# Main.net
KiCad netlist of a schematic drawn in Altium Designer
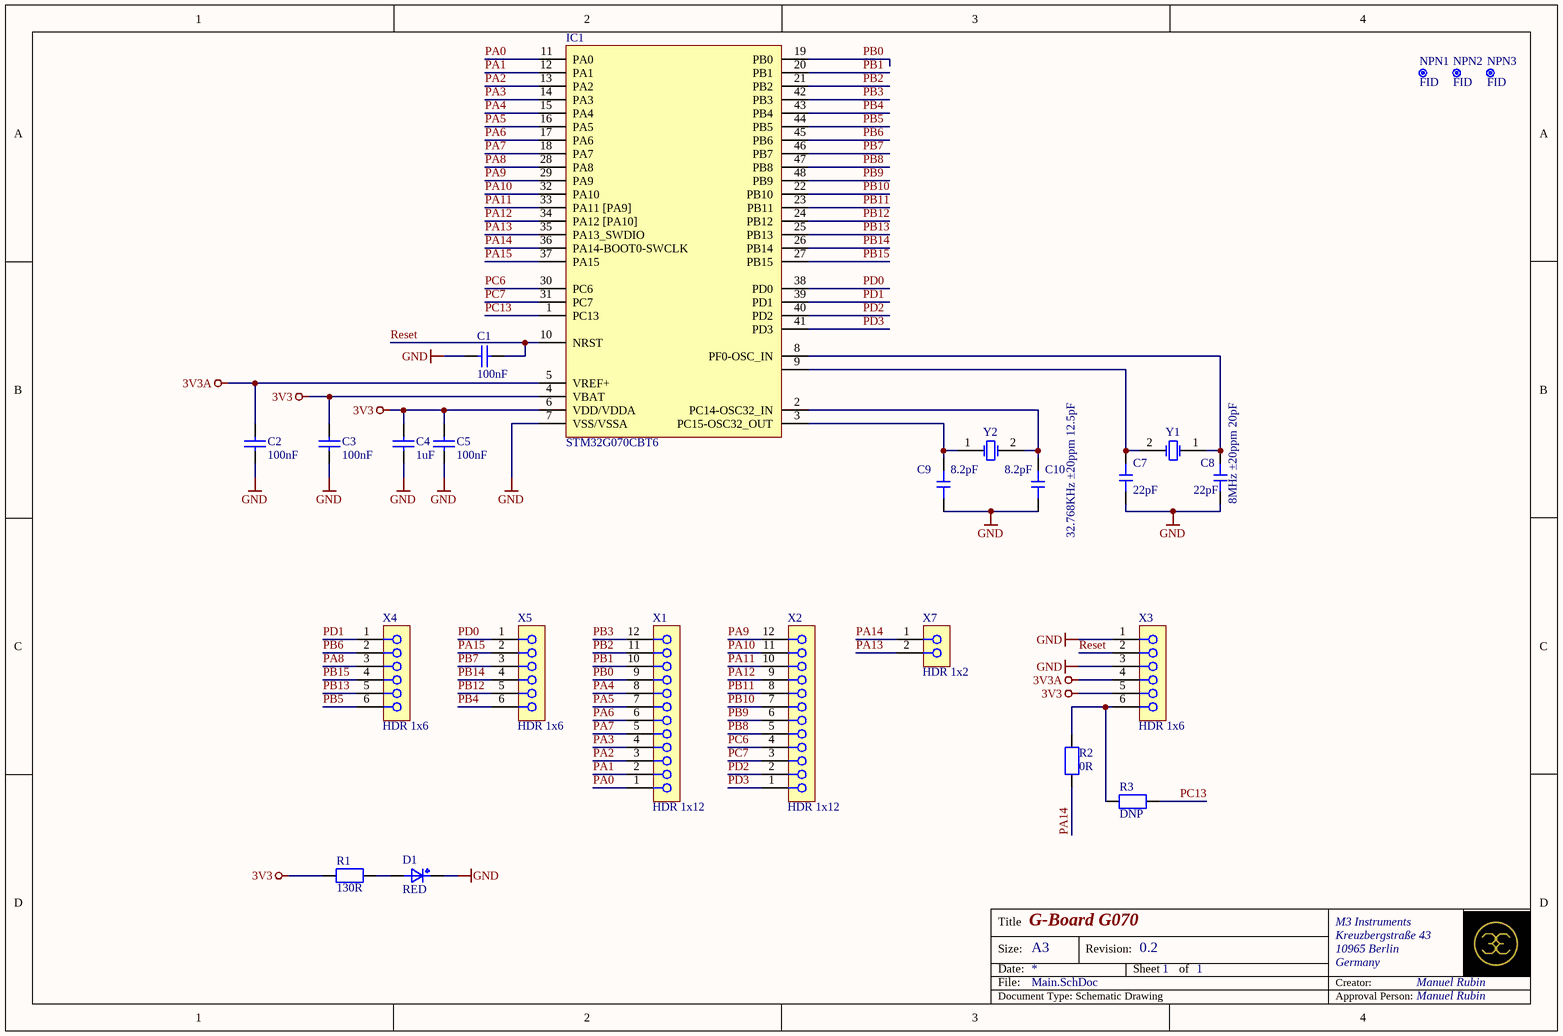
[diagram p0: Main.SchDoc]

(export (version "E")
  (design (tool "Eeschema 10.0.6"))
  (components
    (comp (ref "C1")
      (value "100nF")
      (footprint "CAPC1005X55")
      (description "X7R 100nF ±10% 16V 0402 Multilayer Ceramic Capacitors MLCC - SMD/SMT ROHS")
      (fields
        (field (name "MANUFACTURER") "Samsung Electro-Mechanics")
        (field (name "MANUFACTURER PART NUMBER") "CL05B104KO5NNNC")
      )
      (libsource (lib "Caps") (part "CAP_100nF_0402"))
    )
    (comp (ref "C2")
      (value "100nF")
      (footprint "CAPC1005X55")
      (description "X7R 100nF ±10% 16V 0402 Multilayer Ceramic Capacitors MLCC - SMD/SMT ROHS")
      (fields
        (field (name "MANUFACTURER") "Samsung Electro-Mechanics")
        (field (name "MANUFACTURER PART NUMBER") "CL05B104KO5NNNC")
      )
      (libsource (lib "Caps") (part "CAP_100nF_0402"))
    )
    (comp (ref "C3")
      (value "100nF")
      (footprint "CAPC1005X55")
      (description "X7R 100nF ±10% 16V 0402 Multilayer Ceramic Capacitors MLCC - SMD/SMT ROHS")
      (fields
        (field (name "MANUFACTURER") "Samsung Electro-Mechanics")
        (field (name "MANUFACTURER PART NUMBER") "CL05B104KO5NNNC")
      )
      (libsource (lib "Caps") (part "CAP_100nF_0402"))
    )
    (comp (ref "C4")
      (value "1uF")
      (footprint "CAPC1005X55")
      (description "X5R 25V ±10% 1uF 0402 Multilayer Ceramic Capacitors MLCC - SMD/SMT ROHS")
      (fields
        (field (name "MANUFACTURER") "Samsung Electro-Mechanics")
        (field (name "MANUFACTURER PART NUMBER") "CL05A105KA5NQNC")
      )
      (libsource (lib "Caps") (part "CAP_1uF_0402"))
    )
    (comp (ref "C5")
      (value "100nF")
      (footprint "CAPC1005X55")
      (description "X7R 100nF ±10% 16V 0402 Multilayer Ceramic Capacitors MLCC - SMD/SMT ROHS")
      (fields
        (field (name "MANUFACTURER") "Samsung Electro-Mechanics")
        (field (name "MANUFACTURER PART NUMBER") "CL05B104KO5NNNC")
      )
      (libsource (lib "Caps") (part "CAP_100nF_0402"))
    )
    (comp (ref "C7")
      (value "22pF")
      (footprint "CAPC1608X95N")
      (description "Chip capacitors")
      (fields
        (field (name "MANUFACTURER") "Samsung Electro-Mechanics")
        (field (name "MANUFACTURER PART NUMBER") "CL10C220JB8NNNC")
      )
      (libsource (lib "Caps") (part "CAP_22pF_50V_0603"))
    )
    (comp (ref "C8")
      (value "22pF")
      (footprint "CAPC1608X95N")
      (description "Chip capacitors")
      (fields
        (field (name "MANUFACTURER") "Samsung Electro-Mechanics")
        (field (name "MANUFACTURER PART NUMBER") "CL10C220JB8NNNC")
      )
      (libsource (lib "Caps") (part "CAP_22pF_50V_0603"))
    )
    (comp (ref "C9")
      (value "8.2pF")
      (footprint "CAPC1608X95N")
      (description "Multilayer Ceramic Capacitors MLCC - SMD/SMT 0402 8.0pF 50volts C0G +/-0.5pF")
      (fields
        (field (name "MANUFACTURER") "Guangdong Fenghua Advanced Tech")
        (field (name "MANUFACTURER PART NUMBER") "0603CG8R2C500NT")
      )
      (libsource (lib "Caps") (part "CAP_8p2_50V_0603"))
    )
    (comp (ref "C10")
      (value "8.2pF")
      (footprint "CAPC1608X95N")
      (description "Multilayer Ceramic Capacitors MLCC - SMD/SMT 0402 8.0pF 50volts C0G +/-0.5pF")
      (fields
        (field (name "MANUFACTURER") "Guangdong Fenghua Advanced Tech")
        (field (name "MANUFACTURER PART NUMBER") "0603CG8R2C500NT")
      )
      (libsource (lib "Caps") (part "CAP_8p2_50V_0603"))
    )
    (comp (ref "D1")
      (value "RED")
      (footprint "WL-SMCW_0805")
      (description "Standard LEDs - SMD WL-SMCW SMDMono TpVw Waterclr 0805 Red")
      (fields
        (field (name "MANUFACTURER") "Wurth Elektronik")
        (field (name "MANUFACTURER PART NUMBER") "150080RS75000")
      )
      (libsource (lib "Diodes") (part "LED_0805_RED_AK"))
    )
    (comp (ref "IC1")
      (value "STM32G070CBT6")
      (footprint "LQFP-48_7x7x05P")
      (fields (field (name "MANUFACTURER") "STMicroelectronics"))
      (libsource (lib "ICs") (part "STM32G070CBT6"))
    )
    (comp (ref "NPN1")
      (value "FID")
      (footprint "Fiducial_1mm")
      (libsource (lib "MISC") (part "Fiducial_1mm"))
    )
    (comp (ref "NPN2")
      (value "FID")
      (footprint "Fiducial_1mm")
      (libsource (lib "MISC") (part "Fiducial_1mm"))
    )
    (comp (ref "NPN3")
      (value "FID")
      (footprint "Fiducial_1mm")
      (libsource (lib "MISC") (part "Fiducial_1mm"))
    )
    (comp (ref "R1")
      (value "130R")
      (footprint "RESC2012X70N")
      (description "Dickfilmwiderstände - SMD 1/8watt 130ohms 1% 100ppm")
      (fields
        (field (name "MANUFACTURER") "Vishay / Dale")
        (field (name "MANUFACTURER PART NUMBER") "CRCW0805130RFKEA")
      )
      (libsource (lib "Resistors") (part "RES_130R_0805"))
    )
    (comp (ref "R2")
      (value "0R")
      (footprint "RESC1608X55N")
      (description "Thick Film Resistors - SMD 1/10watt ZEROohm Jumper")
      (fields
        (field (name "MANUFACTURER") "Vishay")
        (field (name "MANUFACTURER PART NUMBER") "CRCW06030000Z0EA")
      )
      (libsource (lib "Resistors") (part "RES_0R_0603"))
    )
    (comp (ref "R3")
      (value "DNP")
      (footprint "RESC1608X55N")
      (description "Resistor SMD 0603 - not populated")
      (libsource (lib "Resistors") (part "RES_DNF_0603"))
    )
    (comp (ref "X1")
      (value "HDR 1x12")
      (footprint "61301211121_no")
      (description "Board-to-Board-Steckverbinder, 2.54 mm, 12 Kontakt(e), Stiftleiste 1-Reihig")
      (fields (field (name "MANUFACTURER") "WE") (field (name "MANUFACTURER PART NUMBER") "61301211121"))
      (libsource (lib "Connectors") (part "CON_HEADER_1X12_no_overlay"))
    )
    (comp (ref "X2")
      (value "HDR 1x12")
      (footprint "61301211121_no")
      (description "Board-to-Board-Steckverbinder, 2.54 mm, 12 Kontakt(e), Stiftleiste 1-Reihig")
      (fields (field (name "MANUFACTURER") "WE") (field (name "MANUFACTURER PART NUMBER") "61301211121"))
      (libsource (lib "Connectors") (part "CON_HEADER_1X12_no_overlay"))
    )
    (comp (ref "X3")
      (value "HDR 1x6")
      (footprint "61300611121_no")
      (description "Board-to-Board-Steckverbinder, 2.54 mm, 6 Kontakt(e), Stiftleiste 1-Reihig")
      (fields (field (name "MANUFACTURER") "WE") (field (name "MANUFACTURER PART NUMBER") "61300611121"))
      (libsource (lib "Connectors") (part "CON_HEADER_1X6_no_overlay"))
    )
    (comp (ref "X4")
      (value "HDR 1x6")
      (footprint "61300611121_no")
      (description "Board-to-Board-Steckverbinder, 2.54 mm, 6 Kontakt(e), Stiftleiste 1-Reihig")
      (fields (field (name "MANUFACTURER") "WE") (field (name "MANUFACTURER PART NUMBER") "61300611121"))
      (libsource (lib "Connectors") (part "CON_HEADER_1X6_no_overlay"))
    )
    (comp (ref "X5")
      (value "HDR 1x6")
      (footprint "61300611121_no")
      (description "Board-to-Board-Steckverbinder, 2.54 mm, 6 Kontakt(e), Stiftleiste 1-Reihig")
      (fields (field (name "MANUFACTURER") "WE") (field (name "MANUFACTURER PART NUMBER") "61300611121"))
      (libsource (lib "Connectors") (part "CON_HEADER_1X6_no_overlay"))
    )
    (comp (ref "X7")
      (value "HDR 1x2")
      (footprint "CON_HEADER2.54_1x2W_no")
      (description "Board-to-Board-Steckverbinder, 2.54 mm, 2 Kontakt(e), Stiftleiste 1-Reihig")
      (fields
        (field (name "MANUFACTURER") "Samtec")
        (field (name "MANUFACTURER PART NUMBER") "TSW-102-07-T-S")
      )
      (libsource (lib "Connectors") (part "CON_HEADER_1X2_no_overlay"))
    )
    (comp (ref "Y1")
      (value "8MHz ±20ppm 20pF")
      (footprint "SMD-5032_2P")
      (description "8MHz SMD Crystal Resonator 20pF ±10ppm ±50ppm -40℃~+85℃ SMD5032-2P Crystals ROHS")
      (fields
        (field (name "MANUFACTURER") "Yangxing Tech")
        (field (name "MANUFACTURER PART NUMBER") "X50328MSB2GI")
      )
      (libsource (lib "MISC") (part "SMD-5032_2P 8MHz 20ppm 20pF"))
    )
    (comp (ref "Y2")
      (value "32.768KHz ±20ppm 12.5pF")
      (footprint "SMD-3215_2P FC - 135")
      (description "32.768kHz SMD Crystal Resonator 12.5pF 70kΩ ±20ppm -40℃~+85℃ SMD3215-2P Crystals ROHS")
      (fields
        (field (name "MANUFACTURER") "Seiko Epson")
        (field (name "MANUFACTURER PART NUMBER") "Q13FC1350000400")
      )
      (libsource (lib "MISC") (part "SMD-3215_2P 32.768KHz 20ppm 12.5pF"))
    )
  )
  (nets
    (net (code "1") (name "/PA0") (class "Default")
      (node (ref "IC1") (pin "11") (pinfunction "PA0_11") (pintype "passive"))
      (node (ref "X1") (pin "1") (pinfunction "1_1") (pintype "passive"))
    )
    (net (code "2") (name "/PA1") (class "Default")
      (node (ref "IC1") (pin "12") (pinfunction "PA1_12") (pintype "passive"))
      (node (ref "X1") (pin "2") (pinfunction "2_2") (pintype "passive"))
    )
    (net (code "3") (name "/PA2") (class "Default")
      (node (ref "IC1") (pin "13") (pinfunction "PA2_13") (pintype "passive"))
      (node (ref "X1") (pin "3") (pinfunction "3_3") (pintype "passive"))
    )
    (net (code "4") (name "/PA3") (class "Default")
      (node (ref "IC1") (pin "14") (pinfunction "PA3_14") (pintype "passive"))
      (node (ref "X1") (pin "4") (pinfunction "4_4") (pintype "passive"))
    )
    (net (code "5") (name "/PA4") (class "Default")
      (node (ref "IC1") (pin "15") (pinfunction "PA4_15") (pintype "passive"))
      (node (ref "X1") (pin "8") (pinfunction "8_8") (pintype "passive"))
    )
    (net (code "6") (name "/PA5") (class "Default")
      (node (ref "IC1") (pin "16") (pinfunction "PA5_16") (pintype "passive"))
      (node (ref "X1") (pin "7") (pinfunction "7_7") (pintype "passive"))
    )
    (net (code "7") (name "/PA6") (class "Default")
      (node (ref "IC1") (pin "17") (pinfunction "PA6_17") (pintype "passive"))
      (node (ref "X1") (pin "6") (pinfunction "6_6") (pintype "passive"))
    )
    (net (code "8") (name "/PA7") (class "Default")
      (node (ref "IC1") (pin "18") (pinfunction "PA7_18") (pintype "passive"))
      (node (ref "X1") (pin "5") (pinfunction "5_5") (pintype "passive"))
    )
    (net (code "9") (name "/PA8") (class "Default")
      (node (ref "IC1") (pin "28") (pinfunction "PA8_28") (pintype "passive"))
      (node (ref "X4") (pin "3") (pinfunction "3_3") (pintype "passive"))
    )
    (net (code "10") (name "/PA9") (class "Default")
      (node (ref "IC1") (pin "29") (pinfunction "PA9_29") (pintype "passive"))
      (node (ref "X2") (pin "12") (pinfunction "12_12") (pintype "passive"))
    )
    (net (code "11") (name "/PA10") (class "Default")
      (node (ref "IC1") (pin "32") (pinfunction "PA10_32") (pintype "passive"))
      (node (ref "X2") (pin "11") (pinfunction "11_11") (pintype "passive"))
    )
    (net (code "12") (name "/PA11") (class "Default")
      (node (ref "IC1") (pin "33") (pinfunction "PA11_[PA9]_33") (pintype "passive"))
      (node (ref "X2") (pin "10") (pinfunction "10_10") (pintype "passive"))
    )
    (net (code "13") (name "/PA12") (class "Default")
      (node (ref "IC1") (pin "34") (pinfunction "PA12_[PA10]_34") (pintype "passive"))
      (node (ref "X2") (pin "9") (pinfunction "9_9") (pintype "passive"))
    )
    (net (code "14") (name "/PA13") (class "Default")
      (node (ref "IC1") (pin "35") (pinfunction "PA13_SWDIO_35") (pintype "power_in"))
      (node (ref "X7") (pin "2") (pinfunction "2_2") (pintype "passive"))
    )
    (net (code "15") (name "/PA14") (class "Default")
      (node (ref "IC1") (pin "36") (pinfunction "PA14-BOOT0-SWCLK_36") (pintype "power_in"))
      (node (ref "R2") (pin "1") (pinfunction "1_1") (pintype "passive"))
      (node (ref "X7") (pin "1") (pinfunction "1_1") (pintype "passive"))
    )
    (net (code "16") (name "/PA15") (class "Default")
      (node (ref "IC1") (pin "37") (pinfunction "PA15_37") (pintype "passive"))
      (node (ref "X5") (pin "2") (pinfunction "2_2") (pintype "passive"))
    )
    (net (code "17") (name "/PB0") (class "Default")
      (node (ref "IC1") (pin "19") (pinfunction "PB0_19") (pintype "passive"))
      (node (ref "X1") (pin "9") (pinfunction "9_9") (pintype "passive"))
    )
    (net (code "18") (name "/PB1") (class "Default")
      (node (ref "IC1") (pin "20") (pinfunction "PB1_20") (pintype "passive"))
      (node (ref "X1") (pin "10") (pinfunction "10_10") (pintype "passive"))
    )
    (net (code "19") (name "/PB2") (class "Default")
      (node (ref "IC1") (pin "21") (pinfunction "PB2_21") (pintype "passive"))
      (node (ref "X1") (pin "11") (pinfunction "11_11") (pintype "passive"))
    )
    (net (code "20") (name "/PB3") (class "Default")
      (node (ref "IC1") (pin "42") (pinfunction "PB3_42") (pintype "passive"))
      (node (ref "X1") (pin "12") (pinfunction "12_12") (pintype "passive"))
    )
    (net (code "21") (name "/PB4") (class "Default")
      (node (ref "IC1") (pin "43") (pinfunction "PB4_43") (pintype "passive"))
      (node (ref "X5") (pin "6") (pinfunction "6_6") (pintype "passive"))
    )
    (net (code "22") (name "/PB5") (class "Default")
      (node (ref "IC1") (pin "44") (pinfunction "PB5_44") (pintype "passive"))
      (node (ref "X4") (pin "6") (pinfunction "6_6") (pintype "passive"))
    )
    (net (code "23") (name "/PB6") (class "Default")
      (node (ref "IC1") (pin "45") (pinfunction "PB6_45") (pintype "passive"))
      (node (ref "X4") (pin "2") (pinfunction "2_2") (pintype "passive"))
    )
    (net (code "24") (name "/PB7") (class "Default")
      (node (ref "IC1") (pin "46") (pinfunction "PB7_46") (pintype "passive"))
      (node (ref "X5") (pin "3") (pinfunction "3_3") (pintype "passive"))
    )
    (net (code "25") (name "/PB8") (class "Default")
      (node (ref "IC1") (pin "47") (pinfunction "PB8_47") (pintype "power_in"))
      (node (ref "X2") (pin "5") (pinfunction "5_5") (pintype "passive"))
    )
    (net (code "26") (name "/PB9") (class "Default")
      (node (ref "IC1") (pin "48") (pinfunction "PB9_48") (pintype "power_in"))
      (node (ref "X2") (pin "6") (pinfunction "6_6") (pintype "passive"))
    )
    (net (code "27") (name "/PB10") (class "Default")
      (node (ref "IC1") (pin "22") (pinfunction "PB10_22") (pintype "passive"))
      (node (ref "X2") (pin "7") (pinfunction "7_7") (pintype "passive"))
    )
    (net (code "28") (name "/PB11") (class "Default")
      (node (ref "IC1") (pin "23") (pinfunction "PB11_23") (pintype "power_in"))
      (node (ref "X2") (pin "8") (pinfunction "8_8") (pintype "passive"))
    )
    (net (code "29") (name "/PB12") (class "Default")
      (node (ref "IC1") (pin "24") (pinfunction "PB12_24") (pintype "power_in"))
      (node (ref "X5") (pin "5") (pinfunction "5_5") (pintype "passive"))
    )
    (net (code "30") (name "/PB13") (class "Default")
      (node (ref "IC1") (pin "25") (pinfunction "PB13_25") (pintype "passive"))
      (node (ref "X4") (pin "5") (pinfunction "5_5") (pintype "passive"))
    )
    (net (code "31") (name "/PB14") (class "Default")
      (node (ref "IC1") (pin "26") (pinfunction "PB14_26") (pintype "passive"))
      (node (ref "X5") (pin "4") (pinfunction "4_4") (pintype "passive"))
    )
    (net (code "32") (name "/PB15") (class "Default")
      (node (ref "IC1") (pin "27") (pinfunction "PB15_27") (pintype "passive"))
      (node (ref "X4") (pin "4") (pinfunction "4_4") (pintype "passive"))
    )
    (net (code "33") (name "/PC6") (class "Default")
      (node (ref "IC1") (pin "30") (pinfunction "PC6_30") (pintype "passive"))
      (node (ref "X2") (pin "4") (pinfunction "4_4") (pintype "passive"))
    )
    (net (code "34") (name "/PC7") (class "Default")
      (node (ref "IC1") (pin "31") (pinfunction "PC7_31") (pintype "passive"))
      (node (ref "X2") (pin "3") (pinfunction "3_3") (pintype "passive"))
    )
    (net (code "35") (name "/PC13") (class "Default")
      (node (ref "IC1") (pin "1") (pinfunction "PC13_1") (pintype "power_in"))
      (node (ref "R3") (pin "2") (pinfunction "2_2") (pintype "passive"))
    )
    (net (code "36") (name "/PD0") (class "Default")
      (node (ref "IC1") (pin "38") (pinfunction "PD0_38") (pintype "passive"))
      (node (ref "X5") (pin "1") (pinfunction "1_1") (pintype "passive"))
    )
    (net (code "37") (name "/PD1") (class "Default")
      (node (ref "IC1") (pin "39") (pinfunction "PD1_39") (pintype "passive"))
      (node (ref "X4") (pin "1") (pinfunction "1_1") (pintype "passive"))
    )
    (net (code "38") (name "/PD2") (class "Default")
      (node (ref "IC1") (pin "40") (pinfunction "PD2_40") (pintype "passive"))
      (node (ref "X2") (pin "2") (pinfunction "2_2") (pintype "passive"))
    )
    (net (code "39") (name "/PD3") (class "Default")
      (node (ref "IC1") (pin "41") (pinfunction "PD3_41") (pintype "passive"))
      (node (ref "X2") (pin "1") (pinfunction "1_1") (pintype "passive"))
    )
    (net (code "40") (name "/Reset") (class "Default")
      (node (ref "C1") (pin "1") (pinfunction "1_1") (pintype "passive"))
      (node (ref "IC1") (pin "10") (pinfunction "NRST_10") (pintype "passive"))
      (node (ref "X3") (pin "2") (pinfunction "2_2") (pintype "passive"))
    )
    (net (code "41") (name "3V3") (class "Default")
      (node (ref "C3") (pin "2") (pinfunction "2_2") (pintype "passive"))
      (node (ref "C4") (pin "2") (pinfunction "2_2") (pintype "passive"))
      (node (ref "C5") (pin "2") (pinfunction "2_2") (pintype "passive"))
      (node (ref "IC1") (pin "4") (pinfunction "VBAT_4") (pintype "passive"))
      (node (ref "IC1") (pin "6") (pinfunction "VDD/VDDA_6") (pintype "passive"))
      (node (ref "R1") (pin "1") (pinfunction "1_1") (pintype "passive"))
      (node (ref "X3") (pin "5") (pinfunction "5_5") (pintype "passive"))
    )
    (net (code "42") (name "3V3A") (class "Default")
      (node (ref "C2") (pin "2") (pinfunction "2_2") (pintype "passive"))
      (node (ref "IC1") (pin "5") (pinfunction "VREF+_5") (pintype "passive"))
      (node (ref "X3") (pin "4") (pinfunction "4_4") (pintype "passive"))
    )
    (net (code "43") (name "GND") (class "Default")
      (node (ref "C1") (pin "2") (pinfunction "2_2") (pintype "passive"))
      (node (ref "C10") (pin "1") (pinfunction "1_1") (pintype "passive"))
      (node (ref "C2") (pin "1") (pinfunction "1_1") (pintype "passive"))
      (node (ref "C3") (pin "1") (pinfunction "1_1") (pintype "passive"))
      (node (ref "C4") (pin "1") (pinfunction "1_1") (pintype "passive"))
      (node (ref "C5") (pin "1") (pinfunction "1_1") (pintype "passive"))
      (node (ref "C7") (pin "2") (pinfunction "2_2") (pintype "passive"))
      (node (ref "C8") (pin "2") (pinfunction "2_2") (pintype "passive"))
      (node (ref "C9") (pin "1") (pinfunction "1_1") (pintype "passive"))
      (node (ref "D1") (pin "K") (pinfunction "K_K") (pintype "passive"))
      (node (ref "IC1") (pin "7") (pinfunction "VSS/VSSA_7") (pintype "passive"))
      (node (ref "X3") (pin "1") (pinfunction "1_1") (pintype "passive"))
      (node (ref "X3") (pin "3") (pinfunction "3_3") (pintype "passive"))
    )
    (net (code "44") (name "Net-(D1-PadA)") (class "Default")
      (node (ref "D1") (pin "A") (pinfunction "A_A") (pintype "passive"))
      (node (ref "R1") (pin "2") (pinfunction "2_2") (pintype "passive"))
    )
    (net (code "45") (name "Net-(IC1-PC14-OSC32_IN)") (class "Default")
      (node (ref "C10") (pin "2") (pinfunction "2_2") (pintype "passive"))
      (node (ref "IC1") (pin "2") (pinfunction "PC14-OSC32_IN_2") (pintype "passive"))
      (node (ref "Y2") (pin "2") (pinfunction "OSC2_2") (pintype "passive"))
    )
    (net (code "46") (name "Net-(IC1-PC15-OSC32_OUT)") (class "Default")
      (node (ref "C9") (pin "2") (pinfunction "2_2") (pintype "passive"))
      (node (ref "IC1") (pin "3") (pinfunction "PC15-OSC32_OUT_3") (pintype "passive"))
      (node (ref "Y2") (pin "1") (pinfunction "OSC1_1") (pintype "passive"))
    )
    (net (code "47") (name "Net-(IC1-PF0-OSC_IN)") (class "Default")
      (node (ref "C8") (pin "1") (pinfunction "1_1") (pintype "passive"))
      (node (ref "IC1") (pin "8") (pinfunction "PF0-OSC_IN_8") (pintype "power_in"))
      (node (ref "Y1") (pin "1") (pinfunction "OSC1_1") (pintype "passive"))
    )
    (net (code "48") (name "Net-(IC1-PF1-OSC_OU'T)") (class "Default")
      (node (ref "C7") (pin "1") (pinfunction "1_1") (pintype "passive"))
      (node (ref "IC1") (pin "9") (pinfunction "PF1-OSC_OU'T_9") (pintype "power_in"))
      (node (ref "Y1") (pin "2") (pinfunction "OSC2_2") (pintype "passive"))
    )
    (net (code "49") (name "Net-(R2-Pad2)") (class "Default")
      (node (ref "R2") (pin "2") (pinfunction "2_2") (pintype "passive"))
      (node (ref "R3") (pin "1") (pinfunction "1_1") (pintype "passive"))
      (node (ref "X3") (pin "6") (pinfunction "6_6") (pintype "passive"))
    )
  )
)
